# CW308T_CEC1702_MICRO.net
KiCad netlist of a schematic drawn in Altium Designer
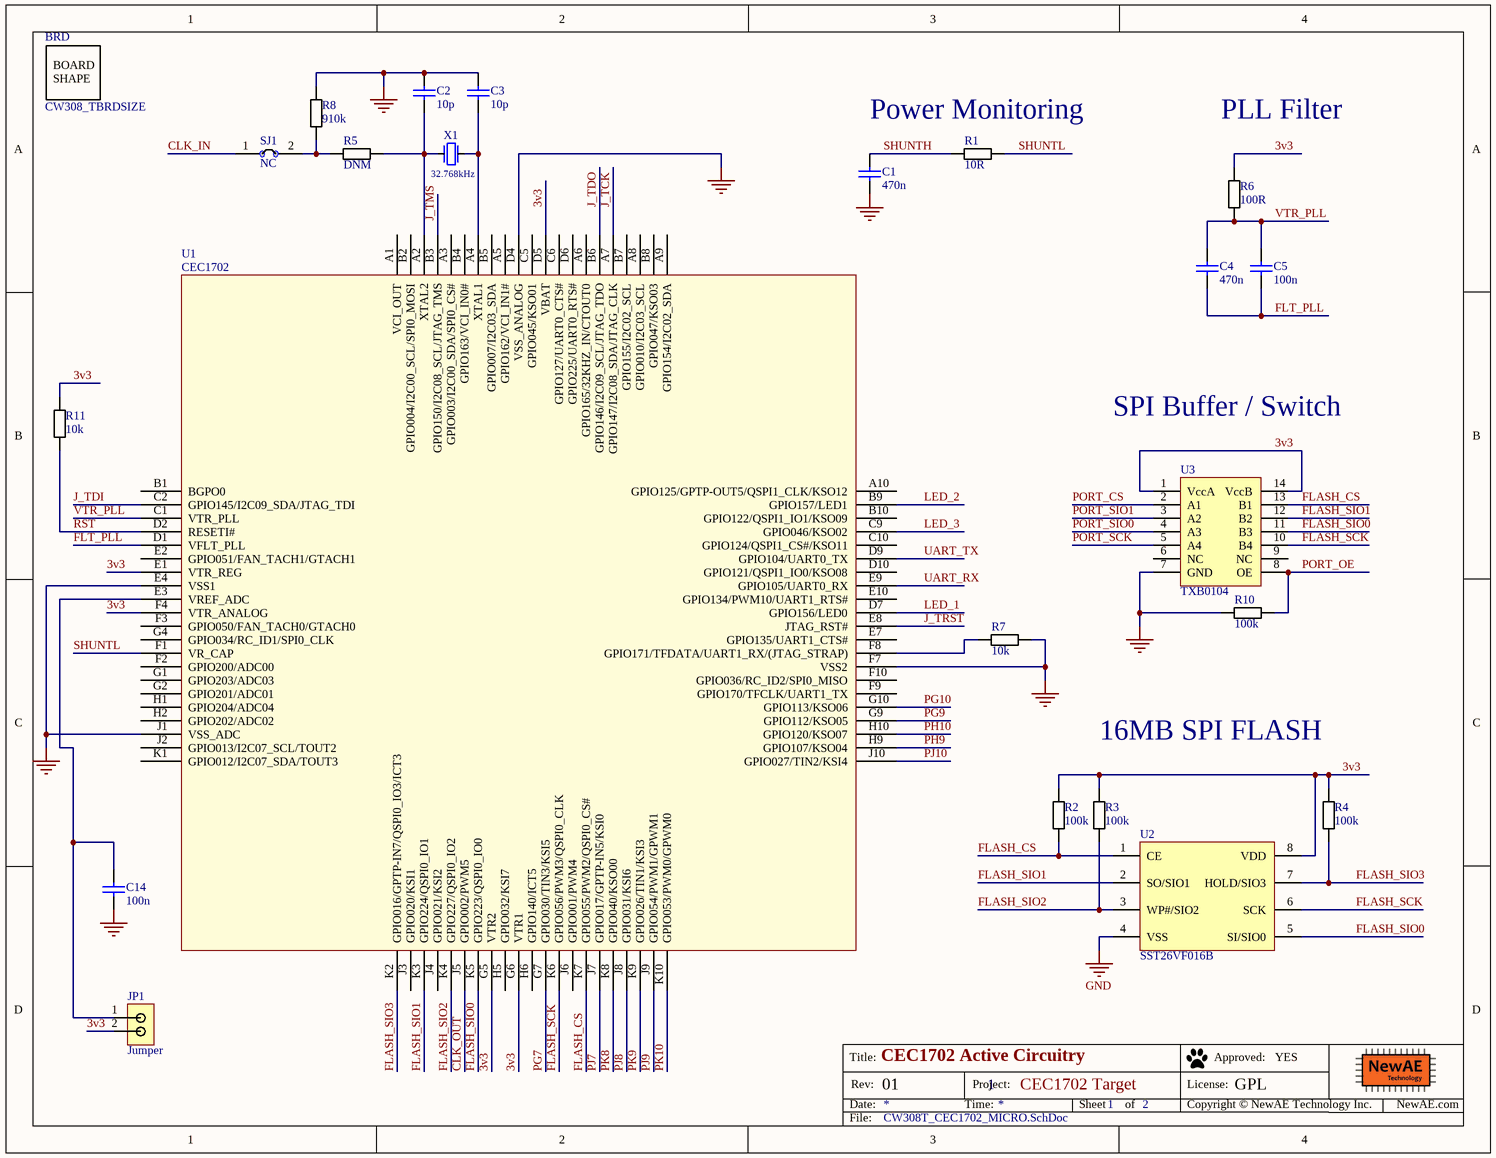
[diagram p0: CW308T_CEC1702_MICRO.SchDoc]

(export (version "E")
  (design (tool "Eeschema 10.0.6"))
  (components
    (comp (ref "BRD")
      (value "CW308_TBRDSIZE")
      (footprint "CW308T_TBOARD_DEFSIZE")
      (description "308T Board Outline (Layer 1)")
      (fields (field (name "PART NUMBER") "CW308T_BRDSHAPE_DEFAULT"))
      (libsource (lib "NewAE_AltiumLib") (part "CW308_TBRDSIZE"))
    )
    (comp (ref "C1")
      (value "470n")
      (footprint "CAPC0603_M")
      (description "470n, 0603, 50V")
      (fields (field (name "PART NUMBER") "CCHIP-470n-0603-50V"))
      (libsource (lib "NewAE_AltiumLib") (part "CAP"))
    )
    (comp (ref "C2")
      (value "10p")
      (footprint "CAPC0603_M")
      (description "10p, 0603")
      (fields (field (name "PART NUMBER") "CCHIP-10p-0603"))
      (libsource (lib "NewAE_AltiumLib") (part "CAP"))
    )
    (comp (ref "C3")
      (value "10p")
      (footprint "CAPC0603_M")
      (description "10p, 0603")
      (fields (field (name "PART NUMBER") "CCHIP-10p-0603"))
      (libsource (lib "NewAE_AltiumLib") (part "CAP"))
    )
    (comp (ref "C4")
      (value "470n")
      (footprint "CAPC0603_M")
      (description "470n, 0603, 50V")
      (fields (field (name "PART NUMBER") "CCHIP-470n-0603-50V"))
      (libsource (lib "NewAE_AltiumLib") (part "CAP"))
    )
    (comp (ref "C5")
      (value "100n")
      (footprint "CAPC0603_M")
      (description "100n, 0603")
      (fields (field (name "PART NUMBER") "CCHIP-100n-0603"))
      (libsource (lib "NewAE_AltiumLib") (part "CAP"))
    )
    (comp (ref "C14")
      (value "100n")
      (footprint "CAPC0603_M")
      (description "100n, 0603")
      (fields (field (name "PART NUMBER") "CCHIP-100n-0603"))
      (libsource (lib "NewAE_AltiumLib") (part "CAP"))
    )
    (comp (ref "JP1")
      (value "Jumper")
      (footprint "2x2.54mm_Header")
      (description "1x2 2.54mm header, male pins")
      (fields (field (name "PART NUMBER") "2_PIN_JUMPER"))
      (libsource (lib "NewAE_AltiumLib") (part "1x2_Pin_Header"))
    )
    (comp (ref "R1")
      (value "10R")
      (footprint "RESC1608X55N")
      (description "10R res, 0603, 1%, 1/10W")
      (fields (field (name "PART NUMBER") "RCHIP-10R-0603") (field (name "TOLERANCE") "1%"))
      (libsource (lib "NewAE_AltiumLib") (part "RES-EU"))
    )
    (comp (ref "R2")
      (value "100k")
      (footprint "RESC1608X55N")
      (description "100k res, 0603, 1%, 1/10W")
      (fields (field (name "PART NUMBER") "RCHIP-100K-0603") (field (name "TOLERANCE") "1%"))
      (libsource (lib "") (part "RES-EU_1"))
    )
    (comp (ref "R3")
      (value "100k")
      (footprint "RESC1608X55N")
      (description "100k res, 0603, 1%, 1/10W")
      (fields (field (name "PART NUMBER") "RCHIP-100K-0603") (field (name "TOLERANCE") "1%"))
      (libsource (lib "") (part "RES-EU_1"))
    )
    (comp (ref "R4")
      (value "100k")
      (footprint "RESC1608X55N")
      (description "100k res, 0603, 1%, 1/10W")
      (fields (field (name "PART NUMBER") "RCHIP-100K-0603") (field (name "TOLERANCE") "1%"))
      (libsource (lib "") (part "RES-EU_1"))
    )
    (comp (ref "R5")
      (value "DNM")
      (footprint "RESC1608X55N")
      (description "100R res, 0603, 1%, 1/10W")
      (fields (field (name "PART NUMBER") "RCHIP-100R-0603") (field (name "TOLERANCE") "1%"))
      (libsource (lib "NewAE_AltiumLib") (part "RES-EU"))
    )
    (comp (ref "R6")
      (value "100R")
      (footprint "RESC1608X55N")
      (description "100R res, 0603, 1%, 1/10W")
      (fields (field (name "PART NUMBER") "RCHIP-100R-0603") (field (name "TOLERANCE") "1%"))
      (libsource (lib "") (part "RES-EU_1"))
    )
    (comp (ref "R7")
      (value "10k")
      (footprint "RESC1608X55N")
      (description "10k res, 0603, 1%, 1/10W")
      (fields (field (name "PART NUMBER") "RCHIP-10K-0603") (field (name "TOLERANCE") "1%"))
      (libsource (lib "NewAE_AltiumLib") (part "RES-EU"))
    )
    (comp (ref "R8")
      (value "910k")
      (footprint "RESC1608X55N")
      (description "910k res, 0603, 1%, 1/10W")
      (fields (field (name "PART NUMBER") "RCHIP-910K-0603") (field (name "TOLERANCE") "1%"))
      (libsource (lib "") (part "RES-EU_1"))
    )
    (comp (ref "R10")
      (value "100k")
      (footprint "RESC1608X55N")
      (description "100k res, 0603, 1%, 1/10W")
      (fields (field (name "PART NUMBER") "RCHIP-100K-0603") (field (name "TOLERANCE") "1%"))
      (libsource (lib "NewAE_AltiumLib") (part "RES-EU"))
    )
    (comp (ref "R11")
      (value "10k")
      (footprint "RESC1608X55N")
      (description "10k res, 0603, 1%, 1/10W")
      (fields (field (name "PART NUMBER") "RCHIP-10K-0603") (field (name "TOLERANCE") "1%"))
      (libsource (lib "") (part "RES-EU_1"))
    )
    (comp (ref "SJ1")
      (value "NC")
      (footprint "SJ_2S_NC")
      (description "Solder Jumper, NC")
      (fields (field (name "PART NUMBER") "SJ_2S"))
      (libsource (lib "NewAE_AltiumLib") (part "SJ_2S"))
    )
    (comp (ref "U1")
      (value "CEC1702")
      (footprint "84L_WFBGA")
      (description "CEC1702, 84WFBGA, microchip hardware crypto")
      (libsource (lib "NewAE_AltiumLib") (part "CEC1702"))
    )
    (comp (ref "U2")
      (value "SST26VF016B")
      (footprint "SOIC8_NARROW")
      (description "IC FLASH 16MBIT 104MHZ 8SOIC")
      (libsource (lib "NewAE_AltiumLib") (part "SST26VF016B"))
    )
    (comp (ref "U3")
      (value "TXB0104")
      (footprint "SOIC14 (R-PDSO-G14)")
      (description "IC 4BIT NON-INV TRANSLTR 14-SOIC")
      (fields (field (name "PART NUMBER") "TXB0104DR"))
      (libsource (lib "NewAE_AltiumLib") (part "TXS104"))
    )
    (comp (ref "X1")
      (value "32.768kHz")
      (footprint "FC-135")
      (description "Crystal, 32kHz, 32.768kHz, 2-pin")
      (fields (field (name "PART NUMBER") "FC-135"))
      (libsource (lib "NewAE_AltiumLib") (part "CRYSTAL_2P"))
    )
  )
  (nets
    (net (code "1") (name "/3v3") (class "Default")
      (node (ref "JP1") (pin "2") (pinfunction "2_2") (pintype "passive"))
      (node (ref "R11") (pin "1") (pinfunction "1_1") (pintype "passive"))
      (node (ref "R2") (pin "1") (pinfunction "1_1") (pintype "passive"))
      (node (ref "R3") (pin "1") (pinfunction "1_1") (pintype "passive"))
      (node (ref "R4") (pin "1") (pinfunction "1_1") (pintype "passive"))
      (node (ref "R6") (pin "1") (pinfunction "1_1") (pintype "passive"))
      (node (ref "U1") (pin "D5") (pinfunction "VBAT_D5") (pintype "passive"))
      (node (ref "U1") (pin "E1") (pinfunction "VTR_REG_E1") (pintype "passive"))
      (node (ref "U1") (pin "F4") (pinfunction "VTR_ANALOG_F4") (pintype "passive"))
      (node (ref "U1") (pin "G5") (pinfunction "VTR2_G5") (pintype "passive"))
      (node (ref "U1") (pin "G6") (pinfunction "VTR1_G6") (pintype "passive"))
      (node (ref "U2") (pin "8") (pinfunction "VDD_8") (pintype "passive"))
      (node (ref "U3") (pin "1") (pinfunction "VccA_1") (pintype "passive"))
      (node (ref "U3") (pin "14") (pinfunction "VccB_14") (pintype "passive"))
    )
    (net (code "2") (name "/CLK_IN") (class "Default")
      (node (ref "SJ1") (pin "1") (pinfunction "1_1") (pintype "passive"))
    )
    (net (code "3") (name "/CLK_OUT") (class "Default")
      (node (ref "U1") (pin "J5") (pinfunction "GPIO002/PWM5_J5") (pintype "passive"))
    )
    (net (code "4") (name "/FLASH_CS") (class "Default")
      (node (ref "R2") (pin "2") (pinfunction "2_2") (pintype "passive"))
      (node (ref "U1") (pin "K7") (pinfunction "GPIO055/PWM2/QSPI0_CS#_K7") (pintype "passive"))
      (node (ref "U2") (pin "1") (pinfunction "CE_1") (pintype "passive"))
      (node (ref "U3") (pin "13") (pinfunction "B1_13") (pintype "passive"))
    )
    (net (code "5") (name "/FLASH_SCK") (class "Default")
      (node (ref "U1") (pin "K6") (pinfunction "GPIO056/PWM3/QSPI0_CLK_K6") (pintype "passive"))
      (node (ref "U2") (pin "6") (pinfunction "SCK_6") (pintype "passive"))
      (node (ref "U3") (pin "10") (pinfunction "B4_10") (pintype "passive"))
    )
    (net (code "6") (name "/FLASH_SIO0") (class "Default")
      (node (ref "U1") (pin "K5") (pinfunction "GPIO223/QSPI0_IO0_K5") (pintype "passive"))
      (node (ref "U2") (pin "5") (pinfunction "SI/SIO0_5") (pintype "passive"))
      (node (ref "U3") (pin "11") (pinfunction "B3_11") (pintype "passive"))
    )
    (net (code "7") (name "/FLASH_SIO1") (class "Default")
      (node (ref "U1") (pin "K3") (pinfunction "GPIO224/QSPI0_IO1_K3") (pintype "passive"))
      (node (ref "U2") (pin "2") (pinfunction "SO/SIO1_2") (pintype "passive"))
      (node (ref "U3") (pin "12") (pinfunction "B2_12") (pintype "passive"))
    )
    (net (code "8") (name "/FLASH_SIO2") (class "Default")
      (node (ref "R3") (pin "2") (pinfunction "2_2") (pintype "passive"))
      (node (ref "U1") (pin "K4") (pinfunction "GPIO227/QSPI0_IO2_K4") (pintype "passive"))
      (node (ref "U2") (pin "3") (pinfunction "WP#/SIO2_3") (pintype "passive"))
    )
    (net (code "9") (name "/FLASH_SIO3") (class "Default")
      (node (ref "R4") (pin "2") (pinfunction "2_2") (pintype "passive"))
      (node (ref "U1") (pin "K2") (pinfunction "GPIO016/GPTP-IN7/QSPI0_IO3/ICT3_K2") (pintype "passive"))
      (node (ref "U2") (pin "7") (pinfunction "HOLD/SIO3_7") (pintype "passive"))
    )
    (net (code "10") (name "/FLT_PLL") (class "Default")
      (node (ref "C4") (pin "2") (pinfunction "2_2") (pintype "passive"))
      (node (ref "C5") (pin "2") (pinfunction "2_2") (pintype "passive"))
      (node (ref "U1") (pin "D1") (pinfunction "VFLT_PLL_D1") (pintype "passive"))
    )
    (net (code "11") (name "/J_TCK") (class "Default")
      (node (ref "U1") (pin "A7") (pinfunction "GPIO147/I2C08_SDA/JTAG_CLK_A7") (pintype "passive"))
    )
    (net (code "12") (name "/J_TDI") (class "Default")
      (node (ref "U1") (pin "C2") (pinfunction "GPIO145/I2C09_SDA/JTAG_TDI_C2") (pintype "passive"))
    )
    (net (code "13") (name "/J_TDO") (class "Default")
      (node (ref "U1") (pin "B6") (pinfunction "GPIO146/I2C09_SCL/JTAG_TDO_B6") (pintype "passive"))
    )
    (net (code "14") (name "/J_TMS") (class "Default")
      (node (ref "U1") (pin "B3") (pinfunction "GPIO150/I2C08_SCL/JTAG_TMS_B3") (pintype "passive"))
    )
    (net (code "15") (name "/J_TRST") (class "Default")
      (node (ref "U1") (pin "E8") (pinfunction "JTAG_RST#_E8") (pintype "passive"))
    )
    (net (code "16") (name "/LED_1") (class "Default")
      (node (ref "U1") (pin "D7") (pinfunction "GPIO156/LED0_D7") (pintype "passive"))
    )
    (net (code "17") (name "/LED_2") (class "Default")
      (node (ref "U1") (pin "B9") (pinfunction "GPIO157/LED1_B9") (pintype "passive"))
    )
    (net (code "18") (name "/LED_3") (class "Default")
      (node (ref "U1") (pin "C9") (pinfunction "GPIO046/KSO02_C9") (pintype "passive"))
    )
    (net (code "19") (name "/PG7") (class "Default")
      (node (ref "U1") (pin "G7") (pinfunction "GPIO030/TIN3/KSI5_G7") (pintype "passive"))
    )
    (net (code "20") (name "/PG9") (class "Default")
      (node (ref "U1") (pin "G9") (pinfunction "GPIO112/KSO05_G9") (pintype "passive"))
    )
    (net (code "21") (name "/PG10") (class "Default")
      (node (ref "U1") (pin "G10") (pinfunction "GPIO113/KSO06_G10") (pintype "passive"))
    )
    (net (code "22") (name "/PH9") (class "Default")
      (node (ref "U1") (pin "H9") (pinfunction "GPIO107/KSO04_H9") (pintype "passive"))
    )
    (net (code "23") (name "/PH10") (class "Default")
      (node (ref "U1") (pin "H10") (pinfunction "GPIO120/KSO07_H10") (pintype "passive"))
    )
    (net (code "24") (name "/PJ7") (class "Default")
      (node (ref "U1") (pin "J7") (pinfunction "GPIO017/GPTP-IN5/KSI0_J7") (pintype "passive"))
    )
    (net (code "25") (name "/PJ8") (class "Default")
      (node (ref "U1") (pin "J8") (pinfunction "GPIO031/KSI6_J8") (pintype "passive"))
    )
    (net (code "26") (name "/PJ9") (class "Default")
      (node (ref "U1") (pin "J9") (pinfunction "GPIO054/PWM1/GPWM1_J9") (pintype "passive"))
    )
    (net (code "27") (name "/PJ10") (class "Default")
      (node (ref "U1") (pin "J10") (pinfunction "GPIO027/TIN2/KSI4_J10") (pintype "passive"))
    )
    (net (code "28") (name "/PK8") (class "Default")
      (node (ref "U1") (pin "K8") (pinfunction "GPIO040/KSO00_K8") (pintype "passive"))
    )
    (net (code "29") (name "/PK9") (class "Default")
      (node (ref "U1") (pin "K9") (pinfunction "GPIO026/TIN1/KSI3_K9") (pintype "passive"))
    )
    (net (code "30") (name "/PK10") (class "Default")
      (node (ref "U1") (pin "K10") (pinfunction "GPIO053/PWM0/GPWM0_K10") (pintype "passive"))
    )
    (net (code "31") (name "/PORT_CS") (class "Default")
      (node (ref "U3") (pin "2") (pinfunction "A1_2") (pintype "passive"))
    )
    (net (code "32") (name "/PORT_OE") (class "Default")
      (node (ref "R10") (pin "2") (pinfunction "2_2") (pintype "passive"))
      (node (ref "U3") (pin "8") (pinfunction "OE_8") (pintype "passive"))
    )
    (net (code "33") (name "/PORT_SCK") (class "Default")
      (node (ref "U3") (pin "5") (pinfunction "A4_5") (pintype "passive"))
    )
    (net (code "34") (name "/PORT_SIO0") (class "Default")
      (node (ref "U3") (pin "4") (pinfunction "A3_4") (pintype "passive"))
    )
    (net (code "35") (name "/PORT_SIO1") (class "Default")
      (node (ref "U3") (pin "3") (pinfunction "A2_3") (pintype "passive"))
    )
    (net (code "36") (name "/RST") (class "Default")
      (node (ref "R11") (pin "2") (pinfunction "2_2") (pintype "passive"))
      (node (ref "U1") (pin "D2") (pinfunction "RESETI#_D2") (pintype "passive"))
    )
    (net (code "37") (name "/SHUNTH") (class "Default")
      (node (ref "C1") (pin "2") (pinfunction "2_2") (pintype "passive"))
      (node (ref "R1") (pin "1") (pinfunction "1_1") (pintype "passive"))
    )
    (net (code "38") (name "/SHUNTL") (class "Default")
      (node (ref "R1") (pin "2") (pinfunction "2_2") (pintype "passive"))
      (node (ref "U1") (pin "F1") (pinfunction "VR_CAP_F1") (pintype "passive"))
    )
    (net (code "39") (name "/UART_RX") (class "Default")
      (node (ref "U1") (pin "E9") (pinfunction "GPIO105/UART0_RX_E9") (pintype "passive"))
    )
    (net (code "40") (name "/UART_TX") (class "Default")
      (node (ref "U1") (pin "D9") (pinfunction "GPIO104/UART0_TX_D9") (pintype "passive"))
    )
    (net (code "41") (name "/VTR_PLL") (class "Default")
      (node (ref "C4") (pin "1") (pinfunction "1_1") (pintype "passive"))
      (node (ref "C5") (pin "1") (pinfunction "1_1") (pintype "passive"))
      (node (ref "R6") (pin "2") (pinfunction "2_2") (pintype "passive"))
      (node (ref "U1") (pin "C1") (pinfunction "VTR_PLL_C1") (pintype "passive"))
    )
    (net (code "42") (name "GND") (class "Default")
      (node (ref "C1") (pin "1") (pinfunction "1_1") (pintype "passive"))
      (node (ref "C14") (pin "2") (pinfunction "2_2") (pintype "passive"))
      (node (ref "C2") (pin "1") (pinfunction "1_1") (pintype "passive"))
      (node (ref "C3") (pin "1") (pinfunction "1_1") (pintype "passive"))
      (node (ref "R10") (pin "1") (pinfunction "1_1") (pintype "passive"))
      (node (ref "R7") (pin "2") (pinfunction "2_2") (pintype "passive"))
      (node (ref "R8") (pin "1") (pinfunction "1_1") (pintype "passive"))
      (node (ref "U1") (pin "D4") (pinfunction "VSS_ANALOG_D4") (pintype "passive"))
      (node (ref "U1") (pin "E4") (pinfunction "VSS1_E4") (pintype "passive"))
      (node (ref "U1") (pin "F7") (pinfunction "VSS2_F7") (pintype "passive"))
      (node (ref "U1") (pin "J1") (pinfunction "VSS_ADC_J1") (pintype "passive"))
      (node (ref "U2") (pin "4") (pinfunction "VSS_4") (pintype "passive"))
      (node (ref "U3") (pin "7") (pinfunction "GND_7") (pintype "passive"))
    )
    (net (code "43") (name "Net-(R5-Pad1)") (class "Default")
      (node (ref "R5") (pin "1") (pinfunction "1_1") (pintype "passive"))
      (node (ref "R8") (pin "2") (pinfunction "2_2") (pintype "passive"))
      (node (ref "SJ1") (pin "2") (pinfunction "2_2") (pintype "passive"))
    )
    (net (code "44") (name "Net-(U1-GPIO171{slash}TFDATA{slash}UART1_RX{slash}(JTAG_STRAP))") (class "Default")
      (node (ref "R7") (pin "1") (pinfunction "1_1") (pintype "passive"))
      (node (ref "U1") (pin "F8") (pinfunction "GPIO171/TFDATA/UART1_RX/(JTAG_STRAP)_F8") (pintype "passive"))
    )
    (net (code "45") (name "Net-(U1-VREF_ADC)") (class "Default")
      (node (ref "C14") (pin "1") (pinfunction "1_1") (pintype "passive"))
      (node (ref "JP1") (pin "1") (pinfunction "1_1") (pintype "passive"))
      (node (ref "U1") (pin "E3") (pinfunction "VREF_ADC_E3") (pintype "passive"))
    )
    (net (code "46") (name "Net-(U1-XTAL1)") (class "Default")
      (node (ref "C3") (pin "2") (pinfunction "2_2") (pintype "passive"))
      (node (ref "U1") (pin "A4") (pinfunction "XTAL1_A4") (pintype "passive"))
      (node (ref "X1") (pin "2") (pinfunction "2_2") (pintype "passive"))
    )
    (net (code "47") (name "Net-(U1-XTAL2)") (class "Default")
      (node (ref "C2") (pin "2") (pinfunction "2_2") (pintype "passive"))
      (node (ref "R5") (pin "2") (pinfunction "2_2") (pintype "passive"))
      (node (ref "U1") (pin "A2") (pinfunction "XTAL2_A2") (pintype "passive"))
      (node (ref "X1") (pin "1") (pinfunction "1_1") (pintype "passive"))
    )
    (net (code "48") (name "unconnected-(U1-BGPO0-PadB1)") (class "Default")
      (node (ref "U1") (pin "B1") (pinfunction "BGPO0_B1") (pintype "passive"))
    )
    (net (code "49") (name "unconnected-(U1-GPIO001{slash}PWM4-PadJ6)") (class "Default")
      (node (ref "U1") (pin "J6") (pinfunction "GPIO001/PWM4_J6") (pintype "passive"))
    )
    (net (code "50") (name "unconnected-(U1-GPIO003{slash}I2C00_SDA{slash}SPI0_CS#-PadA3)") (class "Default")
      (node (ref "U1") (pin "A3") (pinfunction "GPIO003/I2C00_SDA/SPI0_CS#_A3") (pintype "passive"))
    )
    (net (code "51") (name "unconnected-(U1-GPIO004{slash}I2C00_SCL{slash}SPI0_MOSI-PadB2)") (class "Default")
      (node (ref "U1") (pin "B2") (pinfunction "GPIO004/I2C00_SCL/SPI0_MOSI_B2") (pintype "passive"))
    )
    (net (code "52") (name "unconnected-(U1-GPIO007{slash}I2C03_SDA-PadB5)") (class "Default")
      (node (ref "U1") (pin "B5") (pinfunction "GPIO007/I2C03_SDA_B5") (pintype "passive"))
    )
    (net (code "53") (name "unconnected-(U1-GPIO010{slash}I2C03_SCL-PadA8)") (class "Default")
      (node (ref "U1") (pin "A8") (pinfunction "GPIO010/I2C03_SCL_A8") (pintype "passive"))
    )
    (net (code "54") (name "unconnected-(U1-GPIO012{slash}I2C07_SDA{slash}TOUT3-PadK1)") (class "Default")
      (node (ref "U1") (pin "K1") (pinfunction "GPIO012/I2C07_SDA/TOUT3_K1") (pintype "passive"))
    )
    (net (code "55") (name "unconnected-(U1-GPIO013{slash}I2C07_SCL{slash}TOUT2-PadJ2)") (class "Default")
      (node (ref "U1") (pin "J2") (pinfunction "GPIO013/I2C07_SCL/TOUT2_J2") (pintype "passive"))
    )
    (net (code "56") (name "unconnected-(U1-GPIO020{slash}KSI1-PadJ3)") (class "Default")
      (node (ref "U1") (pin "J3") (pinfunction "GPIO020/KSI1_J3") (pintype "passive"))
    )
    (net (code "57") (name "unconnected-(U1-GPIO021{slash}KSI2-PadJ4)") (class "Default")
      (node (ref "U1") (pin "J4") (pinfunction "GPIO021/KSI2_J4") (pintype "passive"))
    )
    (net (code "58") (name "unconnected-(U1-GPIO032{slash}KSI7-PadH5)") (class "Default")
      (node (ref "U1") (pin "H5") (pinfunction "GPIO032/KSI7_H5") (pintype "passive"))
    )
    (net (code "59") (name "unconnected-(U1-GPIO034{slash}RC_ID1{slash}SPI0_CLK-PadG4)") (class "Default")
      (node (ref "U1") (pin "G4") (pinfunction "GPIO034/RC_ID1/SPI0_CLK_G4") (pintype "passive"))
    )
    (net (code "60") (name "unconnected-(U1-GPIO036{slash}RC_ID2{slash}SPI0_MISO-PadF10)") (class "Default")
      (node (ref "U1") (pin "F10") (pinfunction "GPIO036/RC_ID2/SPI0_MISO_F10") (pintype "passive"))
    )
    (net (code "61") (name "unconnected-(U1-GPIO045{slash}KSO01-PadC5)") (class "Default")
      (node (ref "U1") (pin "C5") (pinfunction "GPIO045/KSO01_C5") (pintype "passive"))
    )
    (net (code "62") (name "unconnected-(U1-GPIO047{slash}KSO03-PadB8)") (class "Default")
      (node (ref "U1") (pin "B8") (pinfunction "GPIO047/KSO03_B8") (pintype "passive"))
    )
    (net (code "63") (name "unconnected-(U1-GPIO050{slash}FAN_TACH0{slash}GTACH0-PadF3)") (class "Default")
      (node (ref "U1") (pin "F3") (pinfunction "GPIO050/FAN_TACH0/GTACH0_F3") (pintype "passive"))
    )
    (net (code "64") (name "unconnected-(U1-GPIO051{slash}FAN_TACH1{slash}GTACH1-PadE2)") (class "Default")
      (node (ref "U1") (pin "E2") (pinfunction "GPIO051/FAN_TACH1/GTACH1_E2") (pintype "passive"))
    )
    (net (code "65") (name "unconnected-(U1-GPIO121{slash}QSPI1_IO0{slash}KSO08-PadD10)") (class "Default")
      (node (ref "U1") (pin "D10") (pinfunction "GPIO121/QSPI1_IO0/KSO08_D10") (pintype "passive"))
    )
    (net (code "66") (name "unconnected-(U1-GPIO122{slash}QSPI1_IO1{slash}KSO09-PadB10)") (class "Default")
      (node (ref "U1") (pin "B10") (pinfunction "GPIO122/QSPI1_IO1/KSO09_B10") (pintype "passive"))
    )
    (net (code "67") (name "unconnected-(U1-GPIO124{slash}QSPI1_CS#{slash}KSO11-PadC10)") (class "Default")
      (node (ref "U1") (pin "C10") (pinfunction "GPIO124/QSPI1_CS#/KSO11_C10") (pintype "passive"))
    )
    (net (code "68") (name "unconnected-(U1-GPIO125{slash}GPTP-OUT5{slash}QSPI1_CLK{slash}KSO12-PadA10)") (class "Default")
      (node (ref "U1") (pin "A10") (pinfunction "GPIO125/GPTP-OUT5/QSPI1_CLK/KSO12_A10") (pintype "passive"))
    )
    (net (code "69") (name "unconnected-(U1-GPIO127{slash}UART0_CTS#-PadC6)") (class "Default")
      (node (ref "U1") (pin "C6") (pinfunction "GPIO127/UART0_CTS#_C6") (pintype "passive"))
    )
    (net (code "70") (name "unconnected-(U1-GPIO134{slash}PWM10{slash}UART1_RTS#-PadE10)") (class "Default")
      (node (ref "U1") (pin "E10") (pinfunction "GPIO134/PWM10/UART1_RTS#_E10") (pintype "passive"))
    )
    (net (code "71") (name "unconnected-(U1-GPIO135{slash}UART1_CTS#-PadE7)") (class "Default")
      (node (ref "U1") (pin "E7") (pinfunction "GPIO135/UART1_CTS#_E7") (pintype "passive"))
    )
    (net (code "72") (name "unconnected-(U1-GPIO140{slash}ICT5-PadH6)") (class "Default")
      (node (ref "U1") (pin "H6") (pinfunction "GPIO140/ICT5_H6") (pintype "passive"))
    )
    (net (code "73") (name "unconnected-(U1-GPIO154{slash}I2C02_SDA-PadA9)") (class "Default")
      (node (ref "U1") (pin "A9") (pinfunction "GPIO154/I2C02_SDA_A9") (pintype "passive"))
    )
    (net (code "74") (name "unconnected-(U1-GPIO155{slash}I2C02_SCL-PadB7)") (class "Default")
      (node (ref "U1") (pin "B7") (pinfunction "GPIO155/I2C02_SCL_B7") (pintype "passive"))
    )
    (net (code "75") (name "unconnected-(U1-GPIO162{slash}VCI_IN1#-PadA5)") (class "Default")
      (node (ref "U1") (pin "A5") (pinfunction "GPIO162/VCI_IN1#_A5") (pintype "passive"))
    )
    (net (code "76") (name "unconnected-(U1-GPIO163{slash}VCI_IN0#-PadB4)") (class "Default")
      (node (ref "U1") (pin "B4") (pinfunction "GPIO163/VCI_IN0#_B4") (pintype "passive"))
    )
    (net (code "77") (name "unconnected-(U1-GPIO165{slash}32KHZ_IN{slash}CTOUT0-PadA6)") (class "Default")
      (node (ref "U1") (pin "A6") (pinfunction "GPIO165/32KHZ_IN/CTOUT0_A6") (pintype "passive"))
    )
    (net (code "78") (name "unconnected-(U1-GPIO170{slash}TFCLK{slash}UART1_TX-PadF9)") (class "Default")
      (node (ref "U1") (pin "F9") (pinfunction "GPIO170/TFCLK/UART1_TX_F9") (pintype "passive"))
    )
    (net (code "79") (name "unconnected-(U1-GPIO200{slash}ADC00-PadF2)") (class "Default")
      (node (ref "U1") (pin "F2") (pinfunction "GPIO200/ADC00_F2") (pintype "passive"))
    )
    (net (code "80") (name "unconnected-(U1-GPIO201{slash}ADC01-PadG2)") (class "Default")
      (node (ref "U1") (pin "G2") (pinfunction "GPIO201/ADC01_G2") (pintype "passive"))
    )
    (net (code "81") (name "unconnected-(U1-GPIO202{slash}ADC02-PadH2)") (class "Default")
      (node (ref "U1") (pin "H2") (pinfunction "GPIO202/ADC02_H2") (pintype "passive"))
    )
    (net (code "82") (name "unconnected-(U1-GPIO203{slash}ADC03-PadG1)") (class "Default")
      (node (ref "U1") (pin "G1") (pinfunction "GPIO203/ADC03_G1") (pintype "passive"))
    )
    (net (code "83") (name "unconnected-(U1-GPIO204{slash}ADC04-PadH1)") (class "Default")
      (node (ref "U1") (pin "H1") (pinfunction "GPIO204/ADC04_H1") (pintype "passive"))
    )
    (net (code "84") (name "unconnected-(U1-GPIO225{slash}UART0_RTS#-PadD6)") (class "Default")
      (node (ref "U1") (pin "D6") (pinfunction "GPIO225/UART0_RTS#_D6") (pintype "passive"))
    )
    (net (code "85") (name "unconnected-(U1-VCI_OUT-PadA1)") (class "Default")
      (node (ref "U1") (pin "A1") (pinfunction "VCI_OUT_A1") (pintype "power_in"))
    )
    (net (code "86") (name "unconnected-(U3-NC-Pad6)") (class "Default")
      (node (ref "U3") (pin "6") (pinfunction "NC_6") (pintype "passive"))
    )
    (net (code "87") (name "unconnected-(U3-NC-Pad9)") (class "Default")
      (node (ref "U3") (pin "9") (pinfunction "NC_9") (pintype "passive"))
    )
  )
)
